# Lab_1_Schematic_-_2.net
KiCad netlist of a schematic drawn in EasyEDA Pro
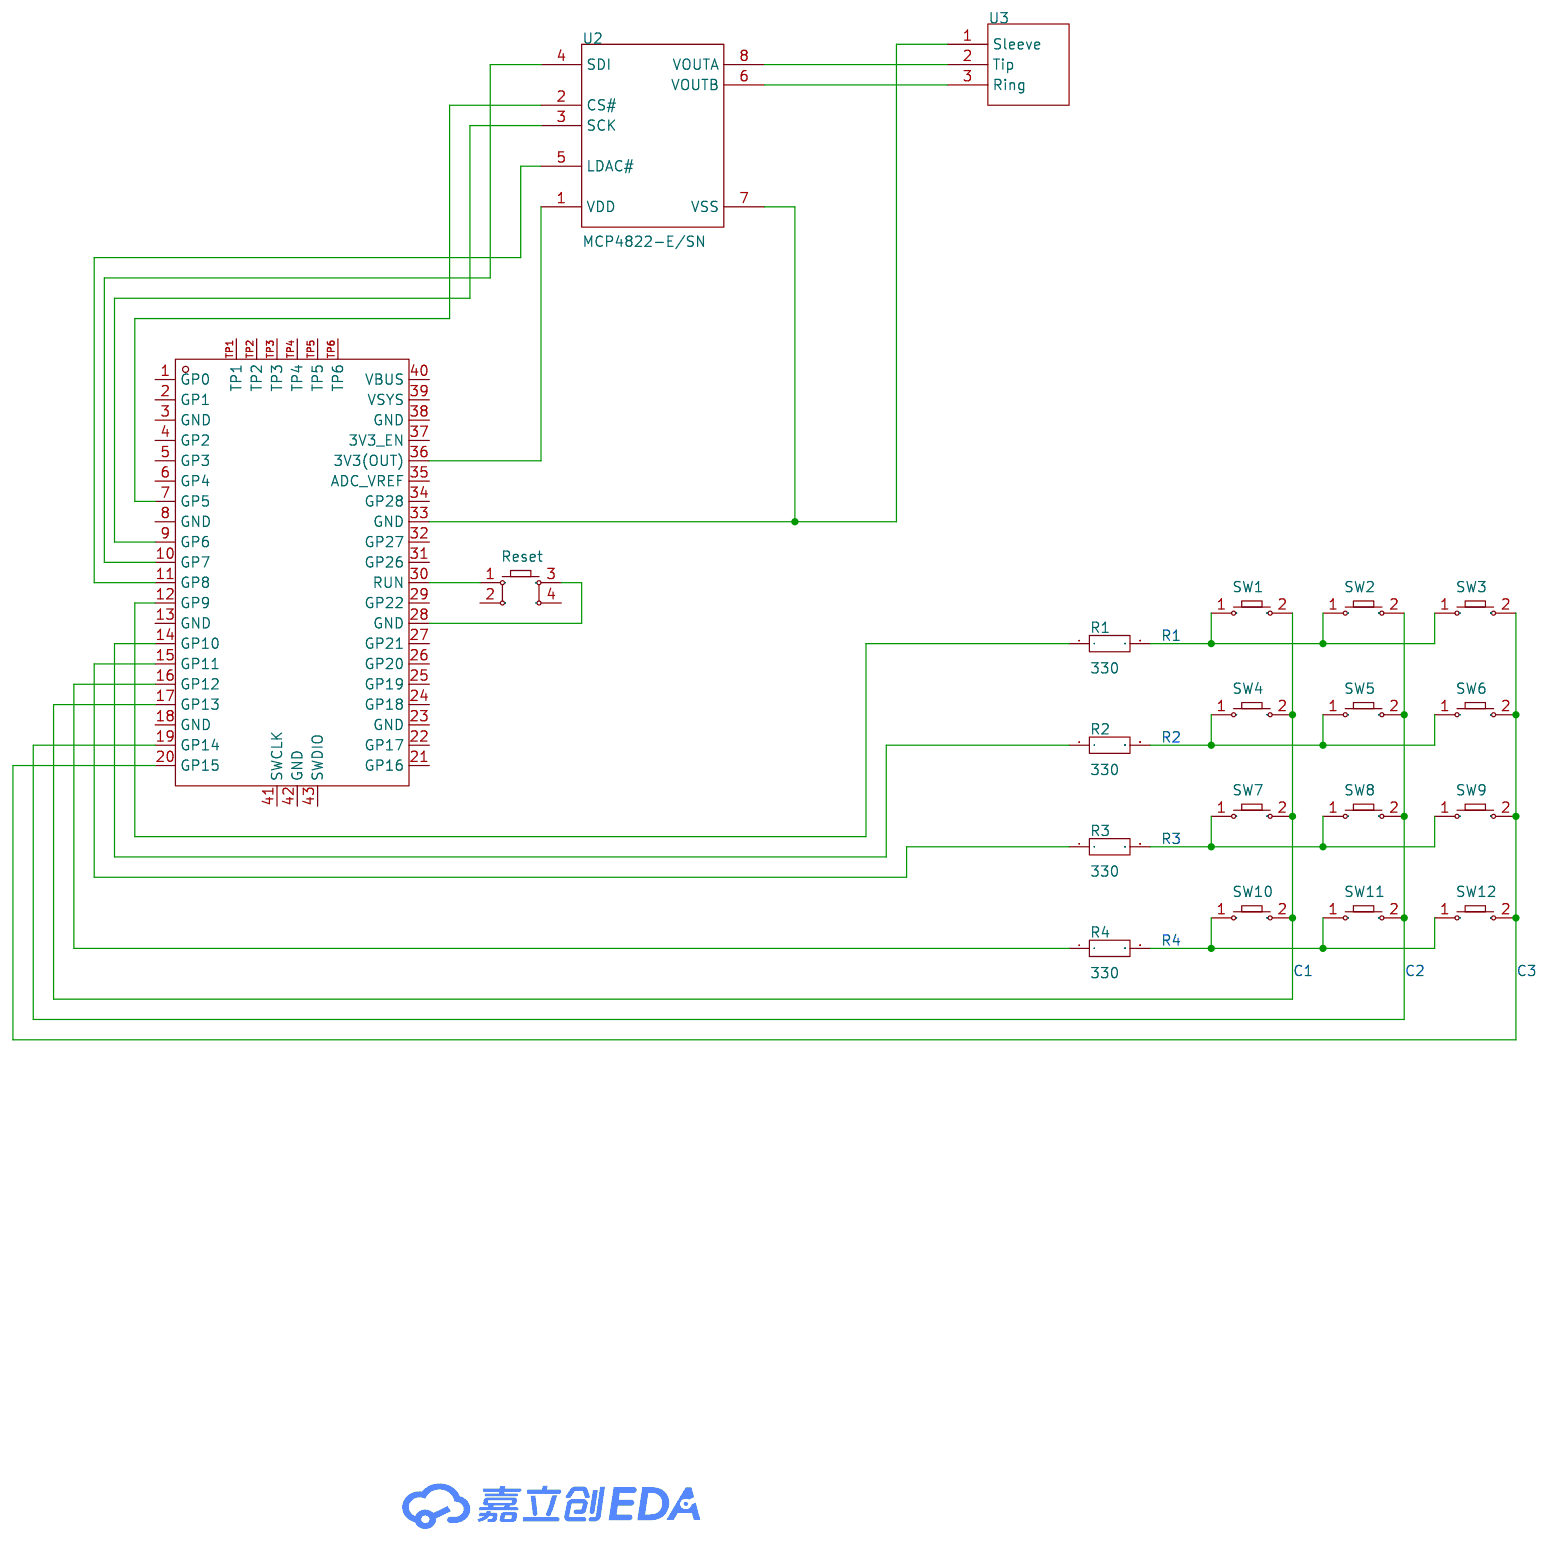
[diagram p0: schematic sheet]

(export (version "E")
  (design (tool "Eeschema 10.0.6"))
  (components
    (comp (ref "R1") (value "330") (footprint "easyedapro:R0603") (libsource (lib "easyedapro") (part "电阻")))
    (comp (ref "R2") (value "330") (footprint "easyedapro:R0603") (libsource (lib "easyedapro") (part "电阻")))
    (comp (ref "R3") (value "330") (footprint "easyedapro:R0603") (libsource (lib "easyedapro") (part "电阻")))
    (comp (ref "R4") (value "330") (footprint "easyedapro:R0603") (libsource (lib "easyedapro") (part "电阻")))
    (comp (ref "Reset")
      (value "~")
      (footprint "easyedapro:Key_SMD_12x12x7.3")
      (libsource (lib "easyedapro") (part "轻触按键"))
    )
    (comp (ref "SW1")
      (value "~")
      (footprint "easyedapro:Key_SMD_3x4x2")
      (libsource (lib "easyedapro") (part "轻触按键x2"))
    )
    (comp (ref "SW2")
      (value "~")
      (footprint "easyedapro:Key_SMD_3x4x2")
      (libsource (lib "easyedapro") (part "轻触按键x2"))
    )
    (comp (ref "SW3")
      (value "~")
      (footprint "easyedapro:Key_SMD_3x4x2")
      (libsource (lib "easyedapro") (part "轻触按键x2"))
    )
    (comp (ref "SW4")
      (value "~")
      (footprint "easyedapro:Key_SMD_3x4x2")
      (libsource (lib "easyedapro") (part "轻触按键x2"))
    )
    (comp (ref "SW5")
      (value "~")
      (footprint "easyedapro:Key_SMD_3x4x2")
      (libsource (lib "easyedapro") (part "轻触按键x2"))
    )
    (comp (ref "SW6")
      (value "~")
      (footprint "easyedapro:Key_SMD_3x4x2")
      (libsource (lib "easyedapro") (part "轻触按键x2"))
    )
    (comp (ref "SW7")
      (value "~")
      (footprint "easyedapro:Key_SMD_3x4x2")
      (libsource (lib "easyedapro") (part "轻触按键x2"))
    )
    (comp (ref "SW8")
      (value "~")
      (footprint "easyedapro:Key_SMD_3x4x2")
      (libsource (lib "easyedapro") (part "轻触按键x2"))
    )
    (comp (ref "SW9")
      (value "~")
      (footprint "easyedapro:Key_SMD_3x4x2")
      (libsource (lib "easyedapro") (part "轻触按键x2"))
    )
    (comp (ref "SW10")
      (value "~")
      (footprint "easyedapro:Key_SMD_3x4x2")
      (libsource (lib "easyedapro") (part "轻触按键x2"))
    )
    (comp (ref "SW11")
      (value "~")
      (footprint "easyedapro:Key_SMD_3x4x2")
      (libsource (lib "easyedapro") (part "轻触按键x2"))
    )
    (comp (ref "SW12")
      (value "~")
      (footprint "easyedapro:Key_SMD_3x4x2")
      (libsource (lib "easyedapro") (part "轻触按键x2"))
    )
    (comp (ref "U1")
      (value "PICO")
      (footprint "easyedapro:COMM-SMD_L51.0-W21.0-P2.54_SC0916")
      (fields (field (name "Manufacturer") "Raspberry Pi(树莓派)"))
      (libsource (lib "easyedapro") (part "PICO"))
    )
    (comp (ref "U2")
      (value "MCP4822-E/SN")
      (footprint "easyedapro:SOIC-8_L4.9-W3.9-P1.27-LS6.0-BL")
      (description "分辨率:12位;接口类型:SPI;工作电压:2.7V~5.5V;稳定时间:4.5us;INL/DNL:12LSB;")
      (fields (field (name "Manufacturer") "MICROCHIP(美国微芯)"))
      (libsource (lib "easyedapro") (part "MCP4822-E/SN"))
    )
    (comp (ref "U3") (value "~") (libsource (lib "easyedapro") (part "3.5mm Socket")))
  )
  (nets
    (net (code "1") (name "Net-(R1-Pad2)") (class "Default")
      (node (ref "R1") (pin "2") (pinfunction "2_2") (pintype "input"))
      (node (ref "SW1") (pin "1") (pinfunction "1_1") (pintype "input"))
      (node (ref "SW2") (pin "1") (pinfunction "1_1") (pintype "input"))
      (node (ref "SW3") (pin "1") (pinfunction "1_1") (pintype "input"))
    )
    (net (code "2") (name "Net-(R2-Pad2)") (class "Default")
      (node (ref "R2") (pin "2") (pinfunction "2_2") (pintype "input"))
      (node (ref "SW4") (pin "1") (pinfunction "1_1") (pintype "input"))
      (node (ref "SW5") (pin "1") (pinfunction "1_1") (pintype "input"))
      (node (ref "SW6") (pin "1") (pinfunction "1_1") (pintype "input"))
    )
    (net (code "3") (name "Net-(R3-Pad2)") (class "Default")
      (node (ref "R3") (pin "2") (pinfunction "2_2") (pintype "input"))
      (node (ref "SW7") (pin "1") (pinfunction "1_1") (pintype "input"))
      (node (ref "SW8") (pin "1") (pinfunction "1_1") (pintype "input"))
      (node (ref "SW9") (pin "1") (pinfunction "1_1") (pintype "input"))
    )
    (net (code "4") (name "Net-(R4-Pad2)") (class "Default")
      (node (ref "R4") (pin "2") (pinfunction "2_2") (pintype "input"))
      (node (ref "SW10") (pin "1") (pinfunction "1_1") (pintype "input"))
      (node (ref "SW11") (pin "1") (pinfunction "1_1") (pintype "input"))
      (node (ref "SW12") (pin "1") (pinfunction "1_1") (pintype "input"))
    )
    (net (code "5") (name "Net-(Reset-Pad3)") (class "Default")
      (node (ref "Reset") (pin "3") (pinfunction "3_3") (pintype "input"))
      (node (ref "U1") (pin "28") (pinfunction "GND_28") (pintype "unspecified"))
    )
    (net (code "6") (name "Net-(U1-3V3(OUT))") (class "Default")
      (node (ref "U1") (pin "36") (pinfunction "3V3(OUT)_36") (pintype "unspecified"))
      (node (ref "U2") (pin "1") (pinfunction "VDD_1") (pintype "unspecified"))
    )
    (net (code "7") (name "Net-(U1-GP5)") (class "Default")
      (node (ref "U1") (pin "7") (pinfunction "GP5_7") (pintype "unspecified"))
      (node (ref "U2") (pin "2") (pinfunction "CS#_2") (pintype "unspecified"))
    )
    (net (code "8") (name "Net-(U1-GP6)") (class "Default")
      (node (ref "U1") (pin "9") (pinfunction "GP6_9") (pintype "unspecified"))
      (node (ref "U2") (pin "3") (pinfunction "SCK_3") (pintype "unspecified"))
    )
    (net (code "9") (name "Net-(U1-GP7)") (class "Default")
      (node (ref "U1") (pin "10") (pinfunction "GP7_10") (pintype "unspecified"))
      (node (ref "U2") (pin "4") (pinfunction "SDI_4") (pintype "unspecified"))
    )
    (net (code "10") (name "Net-(U1-GP8)") (class "Default")
      (node (ref "U1") (pin "11") (pinfunction "GP8_11") (pintype "unspecified"))
      (node (ref "U2") (pin "5") (pinfunction "LDAC#_5") (pintype "unspecified"))
    )
    (net (code "11") (name "Net-(U1-GP9)") (class "Default")
      (node (ref "R1") (pin "1") (pinfunction "1_1") (pintype "input"))
      (node (ref "U1") (pin "12") (pinfunction "GP9_12") (pintype "unspecified"))
    )
    (net (code "12") (name "Net-(U1-GP10)") (class "Default")
      (node (ref "R2") (pin "1") (pinfunction "1_1") (pintype "input"))
      (node (ref "U1") (pin "14") (pinfunction "GP10_14") (pintype "unspecified"))
    )
    (net (code "13") (name "Net-(U1-GP11)") (class "Default")
      (node (ref "R3") (pin "1") (pinfunction "1_1") (pintype "input"))
      (node (ref "U1") (pin "15") (pinfunction "GP11_15") (pintype "unspecified"))
    )
    (net (code "14") (name "Net-(U1-GP12)") (class "Default")
      (node (ref "R4") (pin "1") (pinfunction "1_1") (pintype "input"))
      (node (ref "U1") (pin "16") (pinfunction "GP12_16") (pintype "unspecified"))
    )
    (net (code "15") (name "Net-(U1-GP13)") (class "Default")
      (node (ref "SW1") (pin "2") (pinfunction "2_2") (pintype "input"))
      (node (ref "SW10") (pin "2") (pinfunction "2_2") (pintype "input"))
      (node (ref "SW4") (pin "2") (pinfunction "2_2") (pintype "input"))
      (node (ref "SW7") (pin "2") (pinfunction "2_2") (pintype "input"))
      (node (ref "U1") (pin "17") (pinfunction "GP13_17") (pintype "unspecified"))
    )
    (net (code "16") (name "Net-(U1-GP14)") (class "Default")
      (node (ref "SW11") (pin "2") (pinfunction "2_2") (pintype "input"))
      (node (ref "SW2") (pin "2") (pinfunction "2_2") (pintype "input"))
      (node (ref "SW5") (pin "2") (pinfunction "2_2") (pintype "input"))
      (node (ref "SW8") (pin "2") (pinfunction "2_2") (pintype "input"))
      (node (ref "U1") (pin "19") (pinfunction "GP14_19") (pintype "unspecified"))
    )
    (net (code "17") (name "Net-(U1-GP15)") (class "Default")
      (node (ref "SW12") (pin "2") (pinfunction "2_2") (pintype "input"))
      (node (ref "SW3") (pin "2") (pinfunction "2_2") (pintype "input"))
      (node (ref "SW6") (pin "2") (pinfunction "2_2") (pintype "input"))
      (node (ref "SW9") (pin "2") (pinfunction "2_2") (pintype "input"))
      (node (ref "U1") (pin "20") (pinfunction "GP15_20") (pintype "unspecified"))
    )
    (net (code "18") (name "Net-(U1-RUN)") (class "Default")
      (node (ref "Reset") (pin "1") (pinfunction "1_1") (pintype "input"))
      (node (ref "U1") (pin "30") (pinfunction "RUN_30") (pintype "unspecified"))
    )
    (net (code "19") (name "Net-(U2-VOUTA)") (class "Default")
      (node (ref "U2") (pin "8") (pinfunction "VOUTA_8") (pintype "output"))
      (node (ref "U3") (pin "2") (pinfunction "Tip_2") (pintype "input"))
    )
    (net (code "20") (name "Net-(U2-VOUTB)") (class "Default")
      (node (ref "U2") (pin "6") (pinfunction "VOUTB_6") (pintype "output"))
      (node (ref "U3") (pin "3") (pinfunction "Ring_3") (pintype "input"))
    )
    (net (code "21") (name "Net-(U2-VSS)") (class "Default")
      (node (ref "U1") (pin "33") (pinfunction "GND_33") (pintype "unspecified"))
      (node (ref "U2") (pin "7") (pinfunction "VSS_7") (pintype "unspecified"))
      (node (ref "U3") (pin "1") (pinfunction "Sleeve_1") (pintype "input"))
    )
    (net (code "22") (name "unconnected-(Reset-Pad2)") (class "Default")
      (node (ref "Reset") (pin "2") (pinfunction "2_2") (pintype "input"))
    )
    (net (code "23") (name "unconnected-(Reset-Pad4)") (class "Default")
      (node (ref "Reset") (pin "4") (pinfunction "4_4") (pintype "input"))
    )
    (net (code "24") (name "unconnected-(U1-3V3_EN-Pad37)") (class "Default")
      (node (ref "U1") (pin "37") (pinfunction "3V3_EN_37") (pintype "unspecified"))
    )
    (net (code "25") (name "unconnected-(U1-ADC_VREF-Pad35)") (class "Default")
      (node (ref "U1") (pin "35") (pinfunction "ADC_VREF_35") (pintype "unspecified"))
    )
    (net (code "26") (name "unconnected-(U1-GND-Pad3)") (class "Default")
      (node (ref "U1") (pin "3") (pinfunction "GND_3") (pintype "unspecified"))
    )
    (net (code "27") (name "unconnected-(U1-GND-Pad8)") (class "Default")
      (node (ref "U1") (pin "8") (pinfunction "GND_8") (pintype "unspecified"))
    )
    (net (code "28") (name "unconnected-(U1-GND-Pad13)") (class "Default")
      (node (ref "U1") (pin "13") (pinfunction "GND_13") (pintype "unspecified"))
    )
    (net (code "29") (name "unconnected-(U1-GND-Pad18)") (class "Default")
      (node (ref "U1") (pin "18") (pinfunction "GND_18") (pintype "unspecified"))
    )
    (net (code "30") (name "unconnected-(U1-GND-Pad23)") (class "Default")
      (node (ref "U1") (pin "23") (pinfunction "GND_23") (pintype "unspecified"))
    )
    (net (code "31") (name "unconnected-(U1-GND-Pad38)") (class "Default")
      (node (ref "U1") (pin "38") (pinfunction "GND_38") (pintype "unspecified"))
    )
    (net (code "32") (name "unconnected-(U1-GND-Pad42)") (class "Default")
      (node (ref "U1") (pin "42") (pinfunction "GND_42") (pintype "unspecified"))
    )
    (net (code "33") (name "unconnected-(U1-GP0-Pad1)") (class "Default")
      (node (ref "U1") (pin "1") (pinfunction "GP0_1") (pintype "unspecified"))
    )
    (net (code "34") (name "unconnected-(U1-GP1-Pad2)") (class "Default")
      (node (ref "U1") (pin "2") (pinfunction "GP1_2") (pintype "unspecified"))
    )
    (net (code "35") (name "unconnected-(U1-GP2-Pad4)") (class "Default")
      (node (ref "U1") (pin "4") (pinfunction "GP2_4") (pintype "unspecified"))
    )
    (net (code "36") (name "unconnected-(U1-GP3-Pad5)") (class "Default")
      (node (ref "U1") (pin "5") (pinfunction "GP3_5") (pintype "unspecified"))
    )
    (net (code "37") (name "unconnected-(U1-GP4-Pad6)") (class "Default")
      (node (ref "U1") (pin "6") (pinfunction "GP4_6") (pintype "unspecified"))
    )
    (net (code "38") (name "unconnected-(U1-GP16-Pad21)") (class "Default")
      (node (ref "U1") (pin "21") (pinfunction "GP16_21") (pintype "unspecified"))
    )
    (net (code "39") (name "unconnected-(U1-GP17-Pad22)") (class "Default")
      (node (ref "U1") (pin "22") (pinfunction "GP17_22") (pintype "unspecified"))
    )
    (net (code "40") (name "unconnected-(U1-GP18-Pad24)") (class "Default")
      (node (ref "U1") (pin "24") (pinfunction "GP18_24") (pintype "unspecified"))
    )
    (net (code "41") (name "unconnected-(U1-GP19-Pad25)") (class "Default")
      (node (ref "U1") (pin "25") (pinfunction "GP19_25") (pintype "unspecified"))
    )
    (net (code "42") (name "unconnected-(U1-GP20-Pad26)") (class "Default")
      (node (ref "U1") (pin "26") (pinfunction "GP20_26") (pintype "unspecified"))
    )
    (net (code "43") (name "unconnected-(U1-GP21-Pad27)") (class "Default")
      (node (ref "U1") (pin "27") (pinfunction "GP21_27") (pintype "unspecified"))
    )
    (net (code "44") (name "unconnected-(U1-GP22-Pad29)") (class "Default")
      (node (ref "U1") (pin "29") (pinfunction "GP22_29") (pintype "unspecified"))
    )
    (net (code "45") (name "unconnected-(U1-GP26-Pad31)") (class "Default")
      (node (ref "U1") (pin "31") (pinfunction "GP26_31") (pintype "unspecified"))
    )
    (net (code "46") (name "unconnected-(U1-GP27-Pad32)") (class "Default")
      (node (ref "U1") (pin "32") (pinfunction "GP27_32") (pintype "unspecified"))
    )
    (net (code "47") (name "unconnected-(U1-GP28-Pad34)") (class "Default")
      (node (ref "U1") (pin "34") (pinfunction "GP28_34") (pintype "unspecified"))
    )
    (net (code "48") (name "unconnected-(U1-PadTP1)") (class "Default")
      (node (ref "U1") (pin "TP1") (pinfunction "TP1_TP1") (pintype "unspecified"))
    )
    (net (code "49") (name "unconnected-(U1-PadTP2)") (class "Default")
      (node (ref "U1") (pin "TP2") (pinfunction "TP2_TP2") (pintype "unspecified"))
    )
    (net (code "50") (name "unconnected-(U1-PadTP3)") (class "Default")
      (node (ref "U1") (pin "TP3") (pinfunction "TP3_TP3") (pintype "unspecified"))
    )
    (net (code "51") (name "unconnected-(U1-PadTP4)") (class "Default")
      (node (ref "U1") (pin "TP4") (pinfunction "TP4_TP4") (pintype "unspecified"))
    )
    (net (code "52") (name "unconnected-(U1-PadTP5)") (class "Default")
      (node (ref "U1") (pin "TP5") (pinfunction "TP5_TP5") (pintype "unspecified"))
    )
    (net (code "53") (name "unconnected-(U1-PadTP6)") (class "Default")
      (node (ref "U1") (pin "TP6") (pinfunction "TP6_TP6") (pintype "unspecified"))
    )
    (net (code "54") (name "unconnected-(U1-SWCLK-Pad41)") (class "Default")
      (node (ref "U1") (pin "41") (pinfunction "SWCLK_41") (pintype "unspecified"))
    )
    (net (code "55") (name "unconnected-(U1-SWDIO-Pad43)") (class "Default")
      (node (ref "U1") (pin "43") (pinfunction "SWDIO_43") (pintype "unspecified"))
    )
    (net (code "56") (name "unconnected-(U1-VBUS-Pad40)") (class "Default")
      (node (ref "U1") (pin "40") (pinfunction "VBUS_40") (pintype "unspecified"))
    )
    (net (code "57") (name "unconnected-(U1-VSYS-Pad39)") (class "Default")
      (node (ref "U1") (pin "39") (pinfunction "VSYS_39") (pintype "unspecified"))
    )
  )
)
